# frm-voltrod_4LED.net
KiCad netlist of a schematic drawn in Altium Designer
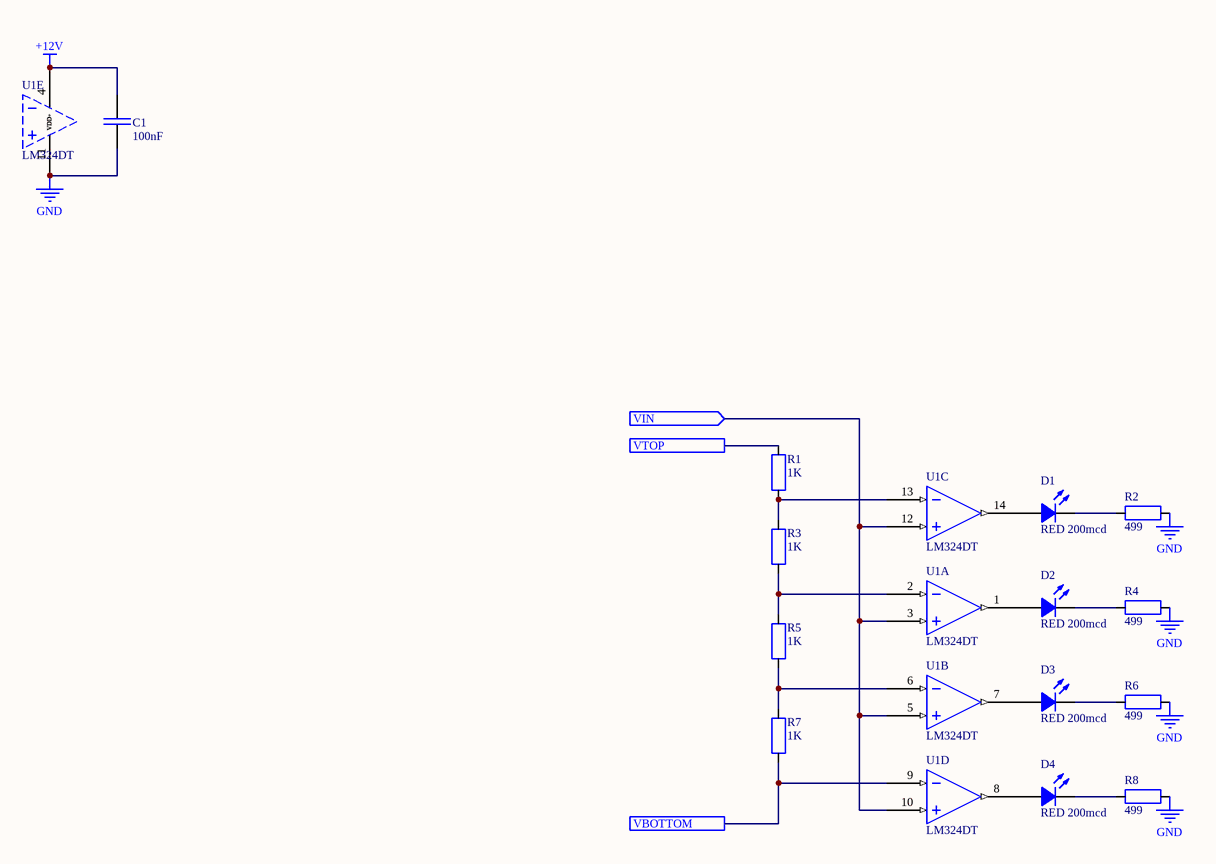
[diagram p0: frm-voltrod_4LED.SchDoc]

(export (version "E")
  (design (tool "Eeschema 10.0.6"))
  (components
    (comp (ref "C1")
      (value "100nF")
      (footprint "CAP 0603_1608")
      (description "CAP SMD MLCC 100nF 25V 0603 X7R")
      (fields (field (name "PART NUMBER") "02841f84-ac15-41b5-9e17-915f8f067828"))
      (libsource (lib "frmdblib") (part "GENERIC_C"))
    )
    (comp (ref "D1")
      (value "RED 200mcd")
      (footprint "ED49B4F6-595F-4D62-96BB-D7184CAA9B94")
      (description "DIODE LED THT 5MM RED 200mcd")
      (fields (field (name "PART NUMBER") "c65ae3d2-9539-4634-8979-616a331b7494"))
      (libsource (lib "frmdblib") (part "GENERIC_D_LED"))
    )
    (comp (ref "D2")
      (value "RED 200mcd")
      (footprint "ED49B4F6-595F-4D62-96BB-D7184CAA9B94")
      (description "DIODE LED THT 5MM RED 200mcd")
      (fields (field (name "PART NUMBER") "c65ae3d2-9539-4634-8979-616a331b7494"))
      (libsource (lib "frmdblib") (part "GENERIC_D_LED"))
    )
    (comp (ref "D3")
      (value "RED 200mcd")
      (footprint "ED49B4F6-595F-4D62-96BB-D7184CAA9B94")
      (description "DIODE LED THT 5MM RED 200mcd")
      (fields (field (name "PART NUMBER") "c65ae3d2-9539-4634-8979-616a331b7494"))
      (libsource (lib "frmdblib") (part "GENERIC_D_LED"))
    )
    (comp (ref "D4")
      (value "RED 200mcd")
      (footprint "ED49B4F6-595F-4D62-96BB-D7184CAA9B94")
      (description "DIODE LED THT 5MM RED 200mcd")
      (fields (field (name "PART NUMBER") "c65ae3d2-9539-4634-8979-616a331b7494"))
      (libsource (lib "frmdblib") (part "GENERIC_D_LED"))
    )
    (comp (ref "R1")
      (value "1K")
      (footprint "RES 0603_1608")
      (description "RES SMD 1K OHM 1% 1/10W 0603")
      (fields (field (name "PART NUMBER") "a678220f-9e9d-4863-a833-9993504f723c"))
      (libsource (lib "frmdblib") (part "GENERIC_R"))
    )
    (comp (ref "R2")
      (value "499")
      (footprint "RES 1206_3216")
      (description "RES SMD 499 OHM 1% 1/4W 1206")
      (fields (field (name "PART NUMBER") "c8bf8de8-3430-48dd-94ac-a027709c0c4f"))
      (libsource (lib "frmdblib") (part "GENERIC_R"))
    )
    (comp (ref "R3")
      (value "1K")
      (footprint "RES 0603_1608")
      (description "RES SMD 1K OHM 1% 1/10W 0603")
      (fields (field (name "PART NUMBER") "a678220f-9e9d-4863-a833-9993504f723c"))
      (libsource (lib "frmdblib") (part "GENERIC_R"))
    )
    (comp (ref "R4")
      (value "499")
      (footprint "RES 1206_3216")
      (description "RES SMD 499 OHM 1% 1/4W 1206")
      (fields (field (name "PART NUMBER") "c8bf8de8-3430-48dd-94ac-a027709c0c4f"))
      (libsource (lib "frmdblib") (part "GENERIC_R"))
    )
    (comp (ref "R5")
      (value "1K")
      (footprint "RES 0603_1608")
      (description "RES SMD 1K OHM 1% 1/10W 0603")
      (fields (field (name "PART NUMBER") "a678220f-9e9d-4863-a833-9993504f723c"))
      (libsource (lib "frmdblib") (part "GENERIC_R"))
    )
    (comp (ref "R6")
      (value "499")
      (footprint "RES 1206_3216")
      (description "RES SMD 499 OHM 1% 1/4W 1206")
      (fields (field (name "PART NUMBER") "c8bf8de8-3430-48dd-94ac-a027709c0c4f"))
      (libsource (lib "frmdblib") (part "GENERIC_R"))
    )
    (comp (ref "R7")
      (value "1K")
      (footprint "RES 0603_1608")
      (description "RES SMD 1K OHM 1% 1/10W 0603")
      (fields (field (name "PART NUMBER") "a678220f-9e9d-4863-a833-9993504f723c"))
      (libsource (lib "frmdblib") (part "GENERIC_R"))
    )
    (comp (ref "R8")
      (value "499")
      (footprint "RES 1206_3216")
      (description "RES SMD 499 OHM 1% 1/4W 1206")
      (fields (field (name "PART NUMBER") "c8bf8de8-3430-48dd-94ac-a027709c0c4f"))
      (libsource (lib "frmdblib") (part "GENERIC_R"))
    )
    (comp (ref "U1")
      (value "LM324DT")
      (footprint "34355DA5-B1DA-47C2-A88A-ECF82120A4F7")
      (description "IC SMD OPAMP LM324DT SO-14")
      (fields (field (name "PART NUMBER") "21a85167-c328-42f7-a52e-365842c6dad3"))
      (libsource (lib "frmdblib") (part "B8DB4B19-8E9C-4F46-A390-7A352E041443"))
    )
  )
  (nets
    (net (code "1") (name "+12V") (class "Default")
      (node (ref "C1") (pin "1") (pintype "passive"))
      (node (ref "U1") (pin "4") (pinfunction "VDD+_4") (pintype "power_in"))
    )
    (net (code "2") (name "/VBOTTOM") (class "Default")
      (node (ref "R7") (pin "2") (pintype "passive"))
      (node (ref "U1") (pin "9") (pinfunction "IN-_9") (pintype "input"))
    )
    (net (code "3") (name "/VIN") (class "Default")
      (node (ref "U1") (pin "10") (pinfunction "IN+_10") (pintype "input"))
      (node (ref "U1") (pin "12") (pinfunction "IN+_12") (pintype "input"))
      (node (ref "U1") (pin "3") (pinfunction "IN+_3") (pintype "input"))
      (node (ref "U1") (pin "5") (pinfunction "IN+_5") (pintype "input"))
    )
    (net (code "4") (name "/VTOP") (class "Default") (node (ref "R1") (pin "1") (pintype "passive")))
    (net (code "5") (name "GND") (class "Default")
      (node (ref "C1") (pin "2") (pintype "passive"))
      (node (ref "R2") (pin "2") (pintype "passive"))
      (node (ref "R4") (pin "2") (pintype "passive"))
      (node (ref "R6") (pin "2") (pintype "passive"))
      (node (ref "R8") (pin "2") (pintype "passive"))
      (node (ref "U1") (pin "11") (pinfunction "VDD-_11") (pintype "power_in"))
    )
    (net (code "6") (name "Net-(D1-A)") (class "Default")
      (node (ref "D1") (pin "2") (pinfunction "A_2") (pintype "passive"))
      (node (ref "U1") (pin "14") (pinfunction "OUT_14") (pintype "output"))
    )
    (net (code "7") (name "Net-(D1-K)") (class "Default")
      (node (ref "D1") (pin "1") (pinfunction "K_1") (pintype "passive"))
      (node (ref "R2") (pin "1") (pintype "passive"))
    )
    (net (code "8") (name "Net-(D2-A)") (class "Default")
      (node (ref "D2") (pin "2") (pinfunction "A_2") (pintype "passive"))
      (node (ref "U1") (pin "1") (pinfunction "OUT_1") (pintype "output"))
    )
    (net (code "9") (name "Net-(D2-K)") (class "Default")
      (node (ref "D2") (pin "1") (pinfunction "K_1") (pintype "passive"))
      (node (ref "R4") (pin "1") (pintype "passive"))
    )
    (net (code "10") (name "Net-(D3-A)") (class "Default")
      (node (ref "D3") (pin "2") (pinfunction "A_2") (pintype "passive"))
      (node (ref "U1") (pin "7") (pinfunction "OUT_7") (pintype "output"))
    )
    (net (code "11") (name "Net-(D3-K)") (class "Default")
      (node (ref "D3") (pin "1") (pinfunction "K_1") (pintype "passive"))
      (node (ref "R6") (pin "1") (pintype "passive"))
    )
    (net (code "12") (name "Net-(D4-A)") (class "Default")
      (node (ref "D4") (pin "2") (pinfunction "A_2") (pintype "passive"))
      (node (ref "U1") (pin "8") (pinfunction "OUT_8") (pintype "output"))
    )
    (net (code "13") (name "Net-(D4-K)") (class "Default")
      (node (ref "D4") (pin "1") (pinfunction "K_1") (pintype "passive"))
      (node (ref "R8") (pin "1") (pintype "passive"))
    )
    (net (code "14") (name "Net-(U1A-IN-)") (class "Default")
      (node (ref "R3") (pin "2") (pintype "passive"))
      (node (ref "R5") (pin "1") (pintype "passive"))
      (node (ref "U1") (pin "2") (pinfunction "IN-_2") (pintype "input"))
    )
    (net (code "15") (name "Net-(U1B-IN-)") (class "Default")
      (node (ref "R5") (pin "2") (pintype "passive"))
      (node (ref "R7") (pin "1") (pintype "passive"))
      (node (ref "U1") (pin "6") (pinfunction "IN-_6") (pintype "input"))
    )
    (net (code "16") (name "Net-(U1C-IN-)") (class "Default")
      (node (ref "R1") (pin "2") (pintype "passive"))
      (node (ref "R3") (pin "1") (pintype "passive"))
      (node (ref "U1") (pin "13") (pinfunction "IN-_13") (pintype "input"))
    )
  )
)
